# PROC051D_DUT_Reference.net
KiCad netlist of a schematic drawn in Altium Designer
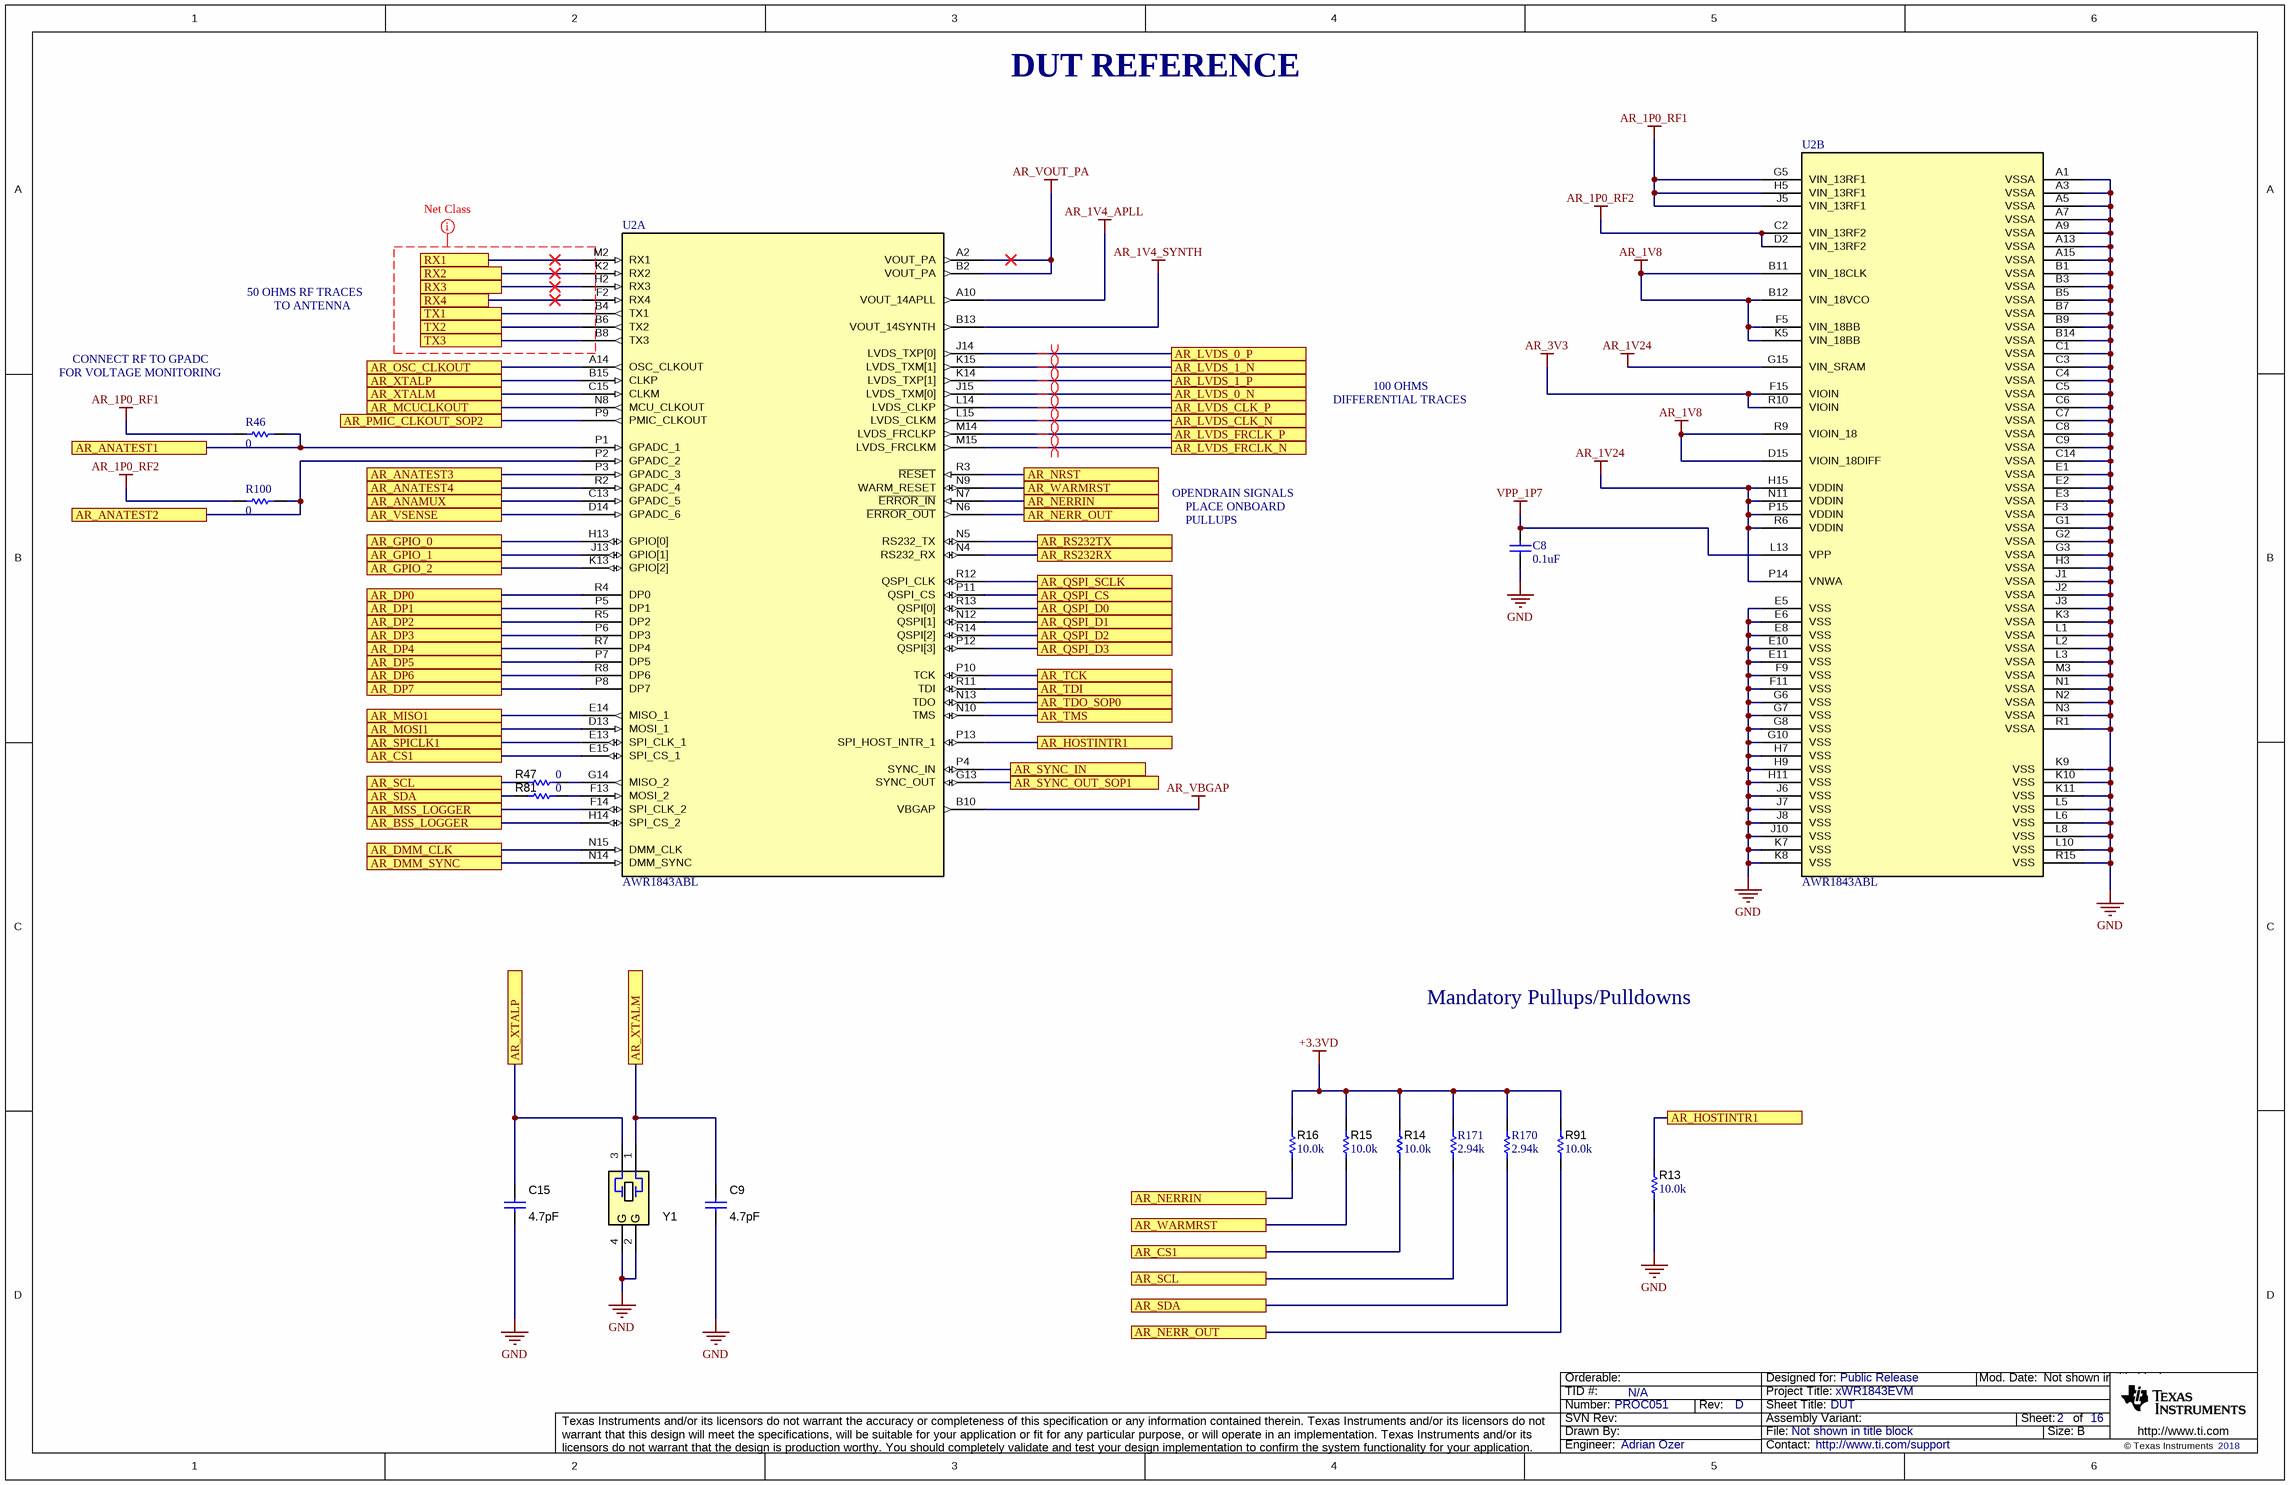
[diagram p0: PROC051D_DUT_Reference.SchDoc]

(export (version "E")
  (design (tool "Eeschema 10.0.6"))
  (components
    (comp (ref "C8")
      (value "GRM033C71A104KE14D")
      (footprint "0201")
      (description "CAP, CERM, 0.1 uF, 10 V,+/- 10%, X7S, 0201")
      (fields
        (field (name "MANUFACTURER") "MuRata")
        (field (name "VALUEDISPLAYED") "0.1uF")
        (field (name "PUBLISHER") "Texas Instruments")
      )
      (libsource (lib "Altium Vault - TI") (part "CMP-0064969-1"))
    )
    (comp (ref "C9")
      (value "GJM1555C1H4R7BB01D")
      (footprint "0402L")
      (description "CAP, CERM, 4.7 pF, 50 V, +/- 2%, C0G/NP0, 0402")
      (fields
        (field (name "MANUFACTURER") "MuRata")
        (field (name "VALUEDISPLAYED") "4.7pF")
        (field (name "PUBLISHER") "Texas Instruments")
      )
      (libsource (lib "Altium Vault - TI") (part "CMP-0006367-2"))
    )
    (comp (ref "C15")
      (value "GJM1555C1H4R7BB01D")
      (footprint "0402L")
      (description "CAP, CERM, 4.7 pF, 50 V, +/- 2%, C0G/NP0, 0402")
      (fields
        (field (name "MANUFACTURER") "MuRata")
        (field (name "VALUEDISPLAYED") "4.7pF")
        (field (name "PUBLISHER") "Texas Instruments")
      )
      (libsource (lib "Altium Vault - TI") (part "CMP-0006367-2"))
    )
    (comp (ref "R13")
      (value "CRCW040210K0FKED")
      (footprint "0402L")
      (description "RES, 10.0 k, 1%, 0.063 W, AEC-Q200 Grade 0, 0402")
      (fields (field (name "MANUFACTURER") "Vishay-Dale") (field (name "VALUEDISPLAYED") "10.0k"))
      (libsource (lib "Altium Vault - TI") (part "Resistor"))
    )
    (comp (ref "R14")
      (value "CRCW040210K0FKED")
      (footprint "0402L")
      (description "RES, 10.0 k, 1%, 0.063 W, AEC-Q200 Grade 0, 0402")
      (fields (field (name "MANUFACTURER") "Vishay-Dale") (field (name "VALUEDISPLAYED") "10.0k"))
      (libsource (lib "Altium Vault - TI") (part "Resistor"))
    )
    (comp (ref "R15")
      (value "CRCW040210K0FKED")
      (footprint "0402L")
      (description "RES, 10.0 k, 1%, 0.063 W, AEC-Q200 Grade 0, 0402")
      (fields (field (name "MANUFACTURER") "Vishay-Dale") (field (name "VALUEDISPLAYED") "10.0k"))
      (libsource (lib "Altium Vault - TI") (part "Resistor"))
    )
    (comp (ref "R16")
      (value "CRCW040210K0FKED")
      (footprint "0402L")
      (description "RES, 10.0 k, 1%, 0.063 W, AEC-Q200 Grade 0, 0402")
      (fields (field (name "MANUFACTURER") "Vishay-Dale") (field (name "VALUEDISPLAYED") "10.0k"))
      (libsource (lib "Altium Vault - TI") (part "Resistor"))
    )
    (comp (ref "R46")
      (value "CRCW04020000Z0ED")
      (footprint "0402")
      (description "RES, 0, 5%, 0.063 W, AEC-Q200 Grade 0, 0402")
      (fields (field (name "MANUFACTURER") "Vishay-Dale") (field (name "VALUEDISPLAYED") "0"))
      (libsource (lib "Altium Vault - TI") (part "CMP-0026822-3"))
    )
    (comp (ref "R47")
      (value "0")
      (footprint "0402L")
      (description "RES, 0, 5%, 0.063 W, AEC-Q200 Grade 0, 0402")
      (fields (field (name "PARTNUMBER") "CRCW04020000Z0ED") (field (name "MANUFACTURER") "Vishay-Dale"))
      (libsource (lib "Altium Vault - TI") (part "Resistor"))
    )
    (comp (ref "R81")
      (value "0")
      (footprint "0402L")
      (description "RES, 0, 5%, 0.063 W, AEC-Q200 Grade 0, 0402")
      (fields (field (name "PARTNUMBER") "CRCW04020000Z0ED") (field (name "MANUFACTURER") "Vishay-Dale"))
      (libsource (lib "Altium Vault - TI") (part "Resistor"))
    )
    (comp (ref "R91")
      (value "CRCW040210K0FKED")
      (footprint "0402L")
      (description "RES, 10.0 k, 1%, 0.063 W, AEC-Q200 Grade 0, 0402")
      (fields (field (name "MANUFACTURER") "Vishay-Dale") (field (name "VALUEDISPLAYED") "10.0k"))
      (libsource (lib "Altium Vault - TI") (part "Resistor"))
    )
    (comp (ref "R100")
      (value "CRCW04020000Z0ED")
      (footprint "0402")
      (description "RES, 0, 5%, 0.063 W, AEC-Q200 Grade 0, 0402")
      (fields (field (name "MANUFACTURER") "Vishay-Dale") (field (name "VALUEDISPLAYED") "0"))
      (libsource (lib "Altium Vault - TI") (part "CMP-0026822-3"))
    )
    (comp (ref "R170")
      (value "CRCW04022K94FKED")
      (footprint "0402")
      (description "RES, 2.94 k, 1%, 0.063 W, AEC-Q200 Grade 0, 0402")
      (fields (field (name "MANUFACTURER") "Vishay-Dale") (field (name "VALUEDISPLAYED") "2.94k"))
      (libsource (lib "Altium Vault - TI") (part "Resistor"))
    )
    (comp (ref "R171")
      (value "CRCW04022K94FKED")
      (footprint "0402")
      (description "RES, 2.94 k, 1%, 0.063 W, AEC-Q200 Grade 0, 0402")
      (fields (field (name "MANUFACTURER") "Vishay-Dale") (field (name "VALUEDISPLAYED") "2.94k"))
      (libsource (lib "Altium Vault - TI") (part "Resistor"))
    )
    (comp (ref "U2")
      (value "AWR1843ABL")
      (footprint "ABL0161B")
      (description "AWR1843ABL, ABL0161B (FCBGA-161)")
      (fields (field (name "PARTNUMBER") "AWR1843ABL") (field (name "MANUFACTURER") "Texas Instruments"))
      (libsource (lib "Altium Vault - TI") (part "AWR1843"))
    )
    (comp (ref "Y1")
      (value "CX3225SA40000D0PTWCC")
      (footprint "Kyocera_CX3225SA")
      (description "Crystal, 40 MHz, 8pF, SMD")
      (fields (field (name "MANUFACTURER") "Kyocera"))
      (libsource (lib "Altium Vault - TI") (part "CMP-0004694-3"))
    )
  )
  (nets
    (net (code "1") (name "+3.3VD") (class "Default")
      (node (ref "R14") (pin "2") (pinfunction "2_2") (pintype "passive"))
      (node (ref "R15") (pin "2") (pinfunction "2_2") (pintype "passive"))
      (node (ref "R16") (pin "2") (pinfunction "2_2") (pintype "passive"))
      (node (ref "R170") (pin "2") (pinfunction "2_2") (pintype "passive"))
      (node (ref "R171") (pin "2") (pinfunction "2_2") (pintype "passive"))
      (node (ref "R91") (pin "2") (pinfunction "2_2") (pintype "passive"))
    )
    (net (code "2") (name "/AR_ANAMUX") (class "Default")
      (node (ref "U2") (pin "C13") (pinfunction "GPADC_5_C13") (pintype "input"))
    )
    (net (code "3") (name "/AR_ANATEST1") (class "Default")
      (node (ref "R46") (pin "1") (pinfunction "1_1") (pintype "passive"))
      (node (ref "U2") (pin "P1") (pinfunction "GPADC_1_P1") (pintype "input"))
    )
    (net (code "4") (name "/AR_ANATEST2") (class "Default")
      (node (ref "R100") (pin "1") (pinfunction "1_1") (pintype "passive"))
      (node (ref "U2") (pin "P2") (pinfunction "GPADC_2_P2") (pintype "input"))
    )
    (net (code "5") (name "/AR_ANATEST3") (class "Default")
      (node (ref "U2") (pin "P3") (pinfunction "GPADC_3_P3") (pintype "input"))
    )
    (net (code "6") (name "/AR_ANATEST4") (class "Default")
      (node (ref "U2") (pin "R2") (pinfunction "GPADC_4_R2") (pintype "input"))
    )
    (net (code "7") (name "/AR_BSS_LOGGER") (class "Default")
      (node (ref "U2") (pin "H14") (pinfunction "SPI_CS_2_H14") (pintype "bidirectional"))
    )
    (net (code "8") (name "/AR_CS1") (class "Default")
      (node (ref "R14") (pin "1") (pinfunction "1_1") (pintype "passive"))
      (node (ref "U2") (pin "E15") (pinfunction "SPI_CS_1_E15") (pintype "bidirectional"))
    )
    (net (code "9") (name "/AR_DMM_CLK") (class "Default")
      (node (ref "U2") (pin "N15") (pinfunction "DMM_CLK_N15") (pintype "input"))
    )
    (net (code "10") (name "/AR_DMM_SYNC") (class "Default")
      (node (ref "U2") (pin "N14") (pinfunction "DMM_SYNC_N14") (pintype "input"))
    )
    (net (code "11") (name "/AR_DP0") (class "Default")
      (node (ref "U2") (pin "R4") (pinfunction "DP0_R4") (pintype "passive"))
    )
    (net (code "12") (name "/AR_DP1") (class "Default")
      (node (ref "U2") (pin "P5") (pinfunction "DP1_P5") (pintype "passive"))
    )
    (net (code "13") (name "/AR_DP2") (class "Default")
      (node (ref "U2") (pin "R5") (pinfunction "DP2_R5") (pintype "passive"))
    )
    (net (code "14") (name "/AR_DP3") (class "Default")
      (node (ref "U2") (pin "P6") (pinfunction "DP3_P6") (pintype "passive"))
    )
    (net (code "15") (name "/AR_DP4") (class "Default")
      (node (ref "U2") (pin "R7") (pinfunction "DP4_R7") (pintype "passive"))
    )
    (net (code "16") (name "/AR_DP5") (class "Default")
      (node (ref "U2") (pin "P7") (pinfunction "DP5_P7") (pintype "passive"))
    )
    (net (code "17") (name "/AR_DP6") (class "Default")
      (node (ref "U2") (pin "R8") (pinfunction "DP6_R8") (pintype "passive"))
    )
    (net (code "18") (name "/AR_DP7") (class "Default")
      (node (ref "U2") (pin "P8") (pinfunction "DP7_P8") (pintype "passive"))
    )
    (net (code "19") (name "/AR_GPIO_0") (class "Default")
      (node (ref "U2") (pin "H13") (pinfunction "GPIO[0]_H13") (pintype "bidirectional"))
    )
    (net (code "20") (name "/AR_GPIO_1") (class "Default")
      (node (ref "U2") (pin "J13") (pinfunction "GPIO[1]_J13") (pintype "bidirectional"))
    )
    (net (code "21") (name "/AR_GPIO_2") (class "Default")
      (node (ref "U2") (pin "K13") (pinfunction "GPIO[2]_K13") (pintype "bidirectional"))
    )
    (net (code "22") (name "/AR_HOSTINTR1") (class "Default")
      (node (ref "R13") (pin "2") (pinfunction "2_2") (pintype "passive"))
      (node (ref "U2") (pin "P13") (pinfunction "SPI_HOST_INTR_1_P13") (pintype "bidirectional"))
    )
    (net (code "23") (name "/AR_LVDS_0_N") (class "Default")
      (node (ref "U2") (pin "J15") (pinfunction "LVDS_TXM[0]_J15") (pintype "output"))
    )
    (net (code "24") (name "/AR_LVDS_0_P") (class "Default")
      (node (ref "U2") (pin "J14") (pinfunction "LVDS_TXP[0]_J14") (pintype "output"))
    )
    (net (code "25") (name "/AR_LVDS_1_N") (class "Default")
      (node (ref "U2") (pin "K15") (pinfunction "LVDS_TXM[1]_K15") (pintype "output"))
    )
    (net (code "26") (name "/AR_LVDS_1_P") (class "Default")
      (node (ref "U2") (pin "K14") (pinfunction "LVDS_TXP[1]_K14") (pintype "output"))
    )
    (net (code "27") (name "/AR_LVDS_CLK_N") (class "Default")
      (node (ref "U2") (pin "L15") (pinfunction "LVDS_CLKM_L15") (pintype "output"))
    )
    (net (code "28") (name "/AR_LVDS_CLK_P") (class "Default")
      (node (ref "U2") (pin "L14") (pinfunction "LVDS_CLKP_L14") (pintype "output"))
    )
    (net (code "29") (name "/AR_LVDS_FRCLK_N") (class "Default")
      (node (ref "U2") (pin "M15") (pinfunction "LVDS_FRCLKM_M15") (pintype "output"))
    )
    (net (code "30") (name "/AR_LVDS_FRCLK_P") (class "Default")
      (node (ref "U2") (pin "M14") (pinfunction "LVDS_FRCLKP_M14") (pintype "output"))
    )
    (net (code "31") (name "/AR_MCUCLKOUT") (class "Default")
      (node (ref "U2") (pin "N8") (pinfunction "MCU_CLKOUT_N8") (pintype "output"))
    )
    (net (code "32") (name "/AR_MISO1") (class "Default")
      (node (ref "U2") (pin "E14") (pinfunction "MISO_1_E14") (pintype "output"))
    )
    (net (code "33") (name "/AR_MOSI1") (class "Default")
      (node (ref "U2") (pin "D13") (pinfunction "MOSI_1_D13") (pintype "input"))
    )
    (net (code "34") (name "/AR_MSS_LOGGER") (class "Default")
      (node (ref "U2") (pin "F14") (pinfunction "SPI_CLK_2_F14") (pintype "bidirectional"))
    )
    (net (code "35") (name "/AR_NERRIN") (class "Default")
      (node (ref "R16") (pin "1") (pinfunction "1_1") (pintype "passive"))
      (node (ref "U2") (pin "N7") (pinfunction "ERROR_IN_N7") (pintype "input"))
    )
    (net (code "36") (name "/AR_NERR_OUT") (class "Default")
      (node (ref "R91") (pin "1") (pinfunction "1_1") (pintype "passive"))
      (node (ref "U2") (pin "N6") (pinfunction "ERROR_OUT_N6") (pintype "output"))
    )
    (net (code "37") (name "/AR_NRST") (class "Default")
      (node (ref "U2") (pin "R3") (pinfunction "RESET_R3") (pintype "input"))
    )
    (net (code "38") (name "/AR_OSC_CLKOUT") (class "Default")
      (node (ref "U2") (pin "A14") (pinfunction "OSC_CLKOUT_A14") (pintype "output"))
    )
    (net (code "39") (name "/AR_PMIC_CLKOUT_SOP2") (class "Default")
      (node (ref "U2") (pin "P9") (pinfunction "PMIC_CLKOUT_P9") (pintype "output"))
    )
    (net (code "40") (name "/AR_QSPI_CS") (class "Default")
      (node (ref "U2") (pin "P11") (pinfunction "QSPI_CS_P11") (pintype "bidirectional"))
    )
    (net (code "41") (name "/AR_QSPI_D0") (class "Default")
      (node (ref "U2") (pin "R13") (pinfunction "QSPI[0]_R13") (pintype "bidirectional"))
    )
    (net (code "42") (name "/AR_QSPI_D1") (class "Default")
      (node (ref "U2") (pin "N12") (pinfunction "QSPI[1]_N12") (pintype "bidirectional"))
    )
    (net (code "43") (name "/AR_QSPI_D2") (class "Default")
      (node (ref "U2") (pin "R14") (pinfunction "QSPI[2]_R14") (pintype "bidirectional"))
    )
    (net (code "44") (name "/AR_QSPI_D3") (class "Default")
      (node (ref "U2") (pin "P12") (pinfunction "QSPI[3]_P12") (pintype "bidirectional"))
    )
    (net (code "45") (name "/AR_QSPI_SCLK") (class "Default")
      (node (ref "U2") (pin "R12") (pinfunction "QSPI_CLK_R12") (pintype "bidirectional"))
    )
    (net (code "46") (name "/AR_RS232RX") (class "Default")
      (node (ref "U2") (pin "N4") (pinfunction "RS232_RX_N4") (pintype "bidirectional"))
    )
    (net (code "47") (name "/AR_RS232TX") (class "Default")
      (node (ref "U2") (pin "N5") (pinfunction "RS232_TX_N5") (pintype "bidirectional"))
    )
    (net (code "48") (name "/AR_SCL") (class "Default")
      (node (ref "R171") (pin "1") (pinfunction "1_1") (pintype "passive"))
      (node (ref "R47") (pin "2") (pinfunction "2_2") (pintype "passive"))
    )
    (net (code "49") (name "/AR_SDA") (class "Default")
      (node (ref "R170") (pin "1") (pinfunction "1_1") (pintype "passive"))
      (node (ref "R81") (pin "2") (pinfunction "2_2") (pintype "passive"))
    )
    (net (code "50") (name "/AR_SPICLK1") (class "Default")
      (node (ref "U2") (pin "E13") (pinfunction "SPI_CLK_1_E13") (pintype "bidirectional"))
    )
    (net (code "51") (name "/AR_SYNC_IN") (class "Default")
      (node (ref "U2") (pin "P4") (pinfunction "SYNC_IN_P4") (pintype "bidirectional"))
    )
    (net (code "52") (name "/AR_SYNC_OUT_SOP1") (class "Default")
      (node (ref "U2") (pin "G13") (pinfunction "SYNC_OUT_G13") (pintype "bidirectional"))
    )
    (net (code "53") (name "/AR_TCK") (class "Default")
      (node (ref "U2") (pin "P10") (pinfunction "TCK_P10") (pintype "bidirectional"))
    )
    (net (code "54") (name "/AR_TDI") (class "Default")
      (node (ref "U2") (pin "R11") (pinfunction "TDI_R11") (pintype "bidirectional"))
    )
    (net (code "55") (name "/AR_TDO_SOP0") (class "Default")
      (node (ref "U2") (pin "N13") (pinfunction "TDO_N13") (pintype "bidirectional"))
    )
    (net (code "56") (name "/AR_TMS") (class "Default")
      (node (ref "U2") (pin "N10") (pinfunction "TMS_N10") (pintype "bidirectional"))
    )
    (net (code "57") (name "/AR_VSENSE") (class "Default")
      (node (ref "U2") (pin "D14") (pinfunction "GPADC_6_D14") (pintype "input"))
    )
    (net (code "58") (name "/AR_WARMRST") (class "Default")
      (node (ref "R15") (pin "1") (pinfunction "1_1") (pintype "passive"))
      (node (ref "U2") (pin "N9") (pinfunction "WARM_RESET_N9") (pintype "bidirectional"))
    )
    (net (code "59") (name "/AR_XTALM") (class "Default")
      (node (ref "C9") (pin "2") (pinfunction "2_2") (pintype "passive"))
      (node (ref "U2") (pin "C15") (pinfunction "CLKM_C15") (pintype "input"))
      (node (ref "Y1") (pin "1") (pinfunction "1_1") (pintype "passive"))
    )
    (net (code "60") (name "/AR_XTALP") (class "Default")
      (node (ref "C15") (pin "2") (pinfunction "2_2") (pintype "passive"))
      (node (ref "U2") (pin "B15") (pinfunction "CLKP_B15") (pintype "input"))
      (node (ref "Y1") (pin "3") (pinfunction "3_3") (pintype "passive"))
    )
    (net (code "61") (name "/RX1") (class "Default")
      (node (ref "U2") (pin "M2") (pinfunction "RX1_M2") (pintype "input"))
    )
    (net (code "62") (name "/RX2") (class "Default")
      (node (ref "U2") (pin "K2") (pinfunction "RX2_K2") (pintype "input"))
    )
    (net (code "63") (name "/RX3") (class "Default")
      (node (ref "U2") (pin "H2") (pinfunction "RX3_H2") (pintype "input"))
    )
    (net (code "64") (name "/RX4") (class "Default")
      (node (ref "U2") (pin "F2") (pinfunction "RX4_F2") (pintype "input"))
    )
    (net (code "65") (name "/TX1") (class "Default")
      (node (ref "U2") (pin "B4") (pinfunction "TX1_B4") (pintype "output"))
    )
    (net (code "66") (name "/TX2") (class "Default")
      (node (ref "U2") (pin "B6") (pinfunction "TX2_B6") (pintype "output"))
    )
    (net (code "67") (name "/TX3") (class "Default")
      (node (ref "U2") (pin "B8") (pinfunction "TX3_B8") (pintype "output"))
    )
    (net (code "68") (name "AR_1P0_RF1") (class "Default")
      (node (ref "R46") (pin "2") (pinfunction "2_2") (pintype "passive"))
      (node (ref "U2") (pin "G5") (pinfunction "VIN_13RF1_G5") (pintype "power_in"))
      (node (ref "U2") (pin "H5") (pinfunction "VIN_13RF1_H5") (pintype "power_in"))
      (node (ref "U2") (pin "J5") (pinfunction "VIN_13RF1_J5") (pintype "power_in"))
    )
    (net (code "69") (name "AR_1P0_RF2") (class "Default")
      (node (ref "R100") (pin "2") (pinfunction "2_2") (pintype "passive"))
      (node (ref "U2") (pin "C2") (pinfunction "VIN_13RF2_C2") (pintype "power_in"))
      (node (ref "U2") (pin "D2") (pinfunction "VIN_13RF2_D2") (pintype "power_in"))
    )
    (net (code "70") (name "AR_1V4_APLL") (class "Default")
      (node (ref "U2") (pin "A10") (pinfunction "VOUT_14APLL_A10") (pintype "output"))
    )
    (net (code "71") (name "AR_1V4_SYNTH") (class "Default")
      (node (ref "U2") (pin "B13") (pinfunction "VOUT_14SYNTH_B13") (pintype "output"))
    )
    (net (code "72") (name "AR_1V8") (class "Default")
      (node (ref "U2") (pin "B11") (pinfunction "VIN_18CLK_B11") (pintype "power_in"))
      (node (ref "U2") (pin "B12") (pinfunction "VIN_18VCO_B12") (pintype "power_in"))
      (node (ref "U2") (pin "D15") (pinfunction "VIOIN_18DIFF_D15") (pintype "power_in"))
      (node (ref "U2") (pin "F5") (pinfunction "VIN_18BB_F5") (pintype "power_in"))
      (node (ref "U2") (pin "K5") (pinfunction "VIN_18BB_K5") (pintype "power_in"))
      (node (ref "U2") (pin "R9") (pinfunction "VIOIN_18_R9") (pintype "power_in"))
    )
    (net (code "73") (name "AR_1V24") (class "Default")
      (node (ref "U2") (pin "G15") (pinfunction "VIN_SRAM_G15") (pintype "power_in"))
      (node (ref "U2") (pin "H15") (pinfunction "VDDIN_H15") (pintype "power_in"))
      (node (ref "U2") (pin "N11") (pinfunction "VDDIN_N11") (pintype "power_in"))
      (node (ref "U2") (pin "P14") (pinfunction "VNWA_P14") (pintype "power_in"))
      (node (ref "U2") (pin "P15") (pinfunction "VDDIN_P15") (pintype "power_in"))
      (node (ref "U2") (pin "R6") (pinfunction "VDDIN_R6") (pintype "power_in"))
    )
    (net (code "74") (name "AR_3V3") (class "Default")
      (node (ref "U2") (pin "F15") (pinfunction "VIOIN_F15") (pintype "power_in"))
      (node (ref "U2") (pin "R10") (pinfunction "VIOIN_R10") (pintype "power_in"))
    )
    (net (code "75") (name "AR_VBGAP") (class "Default")
      (node (ref "U2") (pin "B10") (pinfunction "VBGAP_B10") (pintype "output"))
    )
    (net (code "76") (name "AR_VOUT_PA") (class "Default")
      (node (ref "U2") (pin "A2") (pinfunction "VOUT_PA_A2") (pintype "output"))
      (node (ref "U2") (pin "B2") (pinfunction "VOUT_PA_B2") (pintype "output"))
    )
    (net (code "77") (name "GND") (class "Default")
      (node (ref "C15") (pin "1") (pinfunction "1_1") (pintype "passive"))
      (node (ref "C8") (pin "2") (pinfunction "2_2") (pintype "passive"))
      (node (ref "C9") (pin "1") (pinfunction "1_1") (pintype "passive"))
      (node (ref "R13") (pin "1") (pinfunction "1_1") (pintype "passive"))
      (node (ref "U2") (pin "A1") (pinfunction "VSSA_A1") (pintype "power_in"))
      (node (ref "U2") (pin "A13") (pinfunction "VSSA_A13") (pintype "power_in"))
      (node (ref "U2") (pin "A15") (pinfunction "VSSA_A15") (pintype "power_in"))
      (node (ref "U2") (pin "A3") (pinfunction "VSSA_A3") (pintype "power_in"))
      (node (ref "U2") (pin "A5") (pinfunction "VSSA_A5") (pintype "power_in"))
      (node (ref "U2") (pin "A7") (pinfunction "VSSA_A7") (pintype "power_in"))
      (node (ref "U2") (pin "A9") (pinfunction "VSSA_A9") (pintype "power_in"))
      (node (ref "U2") (pin "B1") (pinfunction "VSSA_B1") (pintype "power_in"))
      (node (ref "U2") (pin "B14") (pinfunction "VSSA_B14") (pintype "power_in"))
      (node (ref "U2") (pin "B3") (pinfunction "VSSA_B3") (pintype "power_in"))
      (node (ref "U2") (pin "B5") (pinfunction "VSSA_B5") (pintype "power_in"))
      (node (ref "U2") (pin "B7") (pinfunction "VSSA_B7") (pintype "power_in"))
      (node (ref "U2") (pin "B9") (pinfunction "VSSA_B9") (pintype "power_in"))
      (node (ref "U2") (pin "C1") (pinfunction "VSSA_C1") (pintype "power_in"))
      (node (ref "U2") (pin "C14") (pinfunction "VSSA_C14") (pintype "power_in"))
      (node (ref "U2") (pin "C3") (pinfunction "VSSA_C3") (pintype "power_in"))
      (node (ref "U2") (pin "C4") (pinfunction "VSSA_C4") (pintype "power_in"))
      (node (ref "U2") (pin "C5") (pinfunction "VSSA_C5") (pintype "power_in"))
      (node (ref "U2") (pin "C6") (pinfunction "VSSA_C6") (pintype "power_in"))
      (node (ref "U2") (pin "C7") (pinfunction "VSSA_C7") (pintype "power_in"))
      (node (ref "U2") (pin "C8") (pinfunction "VSSA_C8") (pintype "power_in"))
      (node (ref "U2") (pin "C9") (pinfunction "VSSA_C9") (pintype "power_in"))
      (node (ref "U2") (pin "E1") (pinfunction "VSSA_E1") (pintype "power_in"))
      (node (ref "U2") (pin "E10") (pinfunction "VSS_E10") (pintype "power_in"))
      (node (ref "U2") (pin "E11") (pinfunction "VSS_E11") (pintype "power_in"))
      (node (ref "U2") (pin "E2") (pinfunction "VSSA_E2") (pintype "power_in"))
      (node (ref "U2") (pin "E3") (pinfunction "VSSA_E3") (pintype "power_in"))
      (node (ref "U2") (pin "E5") (pinfunction "VSS_E5") (pintype "power_in"))
      (node (ref "U2") (pin "E6") (pinfunction "VSS_E6") (pintype "power_in"))
      (node (ref "U2") (pin "E8") (pinfunction "VSS_E8") (pintype "power_in"))
      (node (ref "U2") (pin "F11") (pinfunction "VSS_F11") (pintype "power_in"))
      (node (ref "U2") (pin "F3") (pinfunction "VSSA_F3") (pintype "power_in"))
      (node (ref "U2") (pin "F9") (pinfunction "VSS_F9") (pintype "power_in"))
      (node (ref "U2") (pin "G1") (pinfunction "VSSA_G1") (pintype "power_in"))
      (node (ref "U2") (pin "G10") (pinfunction "VSS_G10") (pintype "power_in"))
      (node (ref "U2") (pin "G2") (pinfunction "VSSA_G2") (pintype "power_in"))
      (node (ref "U2") (pin "G3") (pinfunction "VSSA_G3") (pintype "power_in"))
      (node (ref "U2") (pin "G6") (pinfunction "VSS_G6") (pintype "power_in"))
      (node (ref "U2") (pin "G7") (pinfunction "VSS_G7") (pintype "power_in"))
      (node (ref "U2") (pin "G8") (pinfunction "VSS_G8") (pintype "power_in"))
      (node (ref "U2") (pin "H11") (pinfunction "VSS_H11") (pintype "power_in"))
      (node (ref "U2") (pin "H3") (pinfunction "VSSA_H3") (pintype "power_in"))
      (node (ref "U2") (pin "H7") (pinfunction "VSS_H7") (pintype "power_in"))
      (node (ref "U2") (pin "H9") (pinfunction "VSS_H9") (pintype "power_in"))
      (node (ref "U2") (pin "J1") (pinfunction "VSSA_J1") (pintype "power_in"))
      (node (ref "U2") (pin "J10") (pinfunction "VSS_J10") (pintype "power_in"))
      (node (ref "U2") (pin "J2") (pinfunction "VSSA_J2") (pintype "power_in"))
      (node (ref "U2") (pin "J3") (pinfunction "VSSA_J3") (pintype "power_in"))
      (node (ref "U2") (pin "J6") (pinfunction "VSS_J6") (pintype "power_in"))
      (node (ref "U2") (pin "J7") (pinfunction "VSS_J7") (pintype "power_in"))
      (node (ref "U2") (pin "J8") (pinfunction "VSS_J8") (pintype "power_in"))
      (node (ref "U2") (pin "K10") (pinfunction "VSS_K10") (pintype "power_in"))
      (node (ref "U2") (pin "K11") (pinfunction "VSS_K11") (pintype "power_in"))
      (node (ref "U2") (pin "K3") (pinfunction "VSSA_K3") (pintype "power_in"))
      (node (ref "U2") (pin "K7") (pinfunction "VSS_K7") (pintype "power_in"))
      (node (ref "U2") (pin "K8") (pinfunction "VSS_K8") (pintype "power_in"))
      (node (ref "U2") (pin "K9") (pinfunction "VSS_K9") (pintype "power_in"))
      (node (ref "U2") (pin "L1") (pinfunction "VSSA_L1") (pintype "power_in"))
      (node (ref "U2") (pin "L10") (pinfunction "VSS_L10") (pintype "power_in"))
      (node (ref "U2") (pin "L2") (pinfunction "VSSA_L2") (pintype "power_in"))
      (node (ref "U2") (pin "L3") (pinfunction "VSSA_L3") (pintype "power_in"))
      (node (ref "U2") (pin "L5") (pinfunction "VSS_L5") (pintype "power_in"))
      (node (ref "U2") (pin "L6") (pinfunction "VSS_L6") (pintype "power_in"))
      (node (ref "U2") (pin "L8") (pinfunction "VSS_L8") (pintype "power_in"))
      (node (ref "U2") (pin "M3") (pinfunction "VSSA_M3") (pintype "power_in"))
      (node (ref "U2") (pin "N1") (pinfunction "VSSA_N1") (pintype "power_in"))
      (node (ref "U2") (pin "N2") (pinfunction "VSSA_N2") (pintype "power_in"))
      (node (ref "U2") (pin "N3") (pinfunction "VSSA_N3") (pintype "power_in"))
      (node (ref "U2") (pin "R1") (pinfunction "VSSA_R1") (pintype "power_in"))
      (node (ref "U2") (pin "R15") (pinfunction "VSS_R15") (pintype "power_in"))
      (node (ref "Y1") (pin "2") (pinfunction "GND_2") (pintype "power_in"))
      (node (ref "Y1") (pin "4") (pinfunction "GND_4") (pintype "power_in"))
    )
    (net (code "78") (name "Net-(U2A-MISO_2)") (class "Default")
      (node (ref "R47") (pin "1") (pinfunction "1_1") (pintype "passive"))
      (node (ref "U2") (pin "G14") (pinfunction "MISO_2_G14") (pintype "output"))
    )
    (net (code "79") (name "Net-(U2A-MOSI_2)") (class "Default")
      (node (ref "R81") (pin "1") (pinfunction "1_1") (pintype "passive"))
      (node (ref "U2") (pin "F13") (pinfunction "MOSI_2_F13") (pintype "input"))
    )
    (net (code "80") (name "VPP_1P7") (class "Default")
      (node (ref "C8") (pin "1") (pinfunction "1_1") (pintype "passive"))
      (node (ref "U2") (pin "L13") (pinfunction "VPP_L13") (pintype "power_in"))
    )
  )
)
